# STM32_MCU.net
KiCad netlist of a schematic drawn in Altium Designer
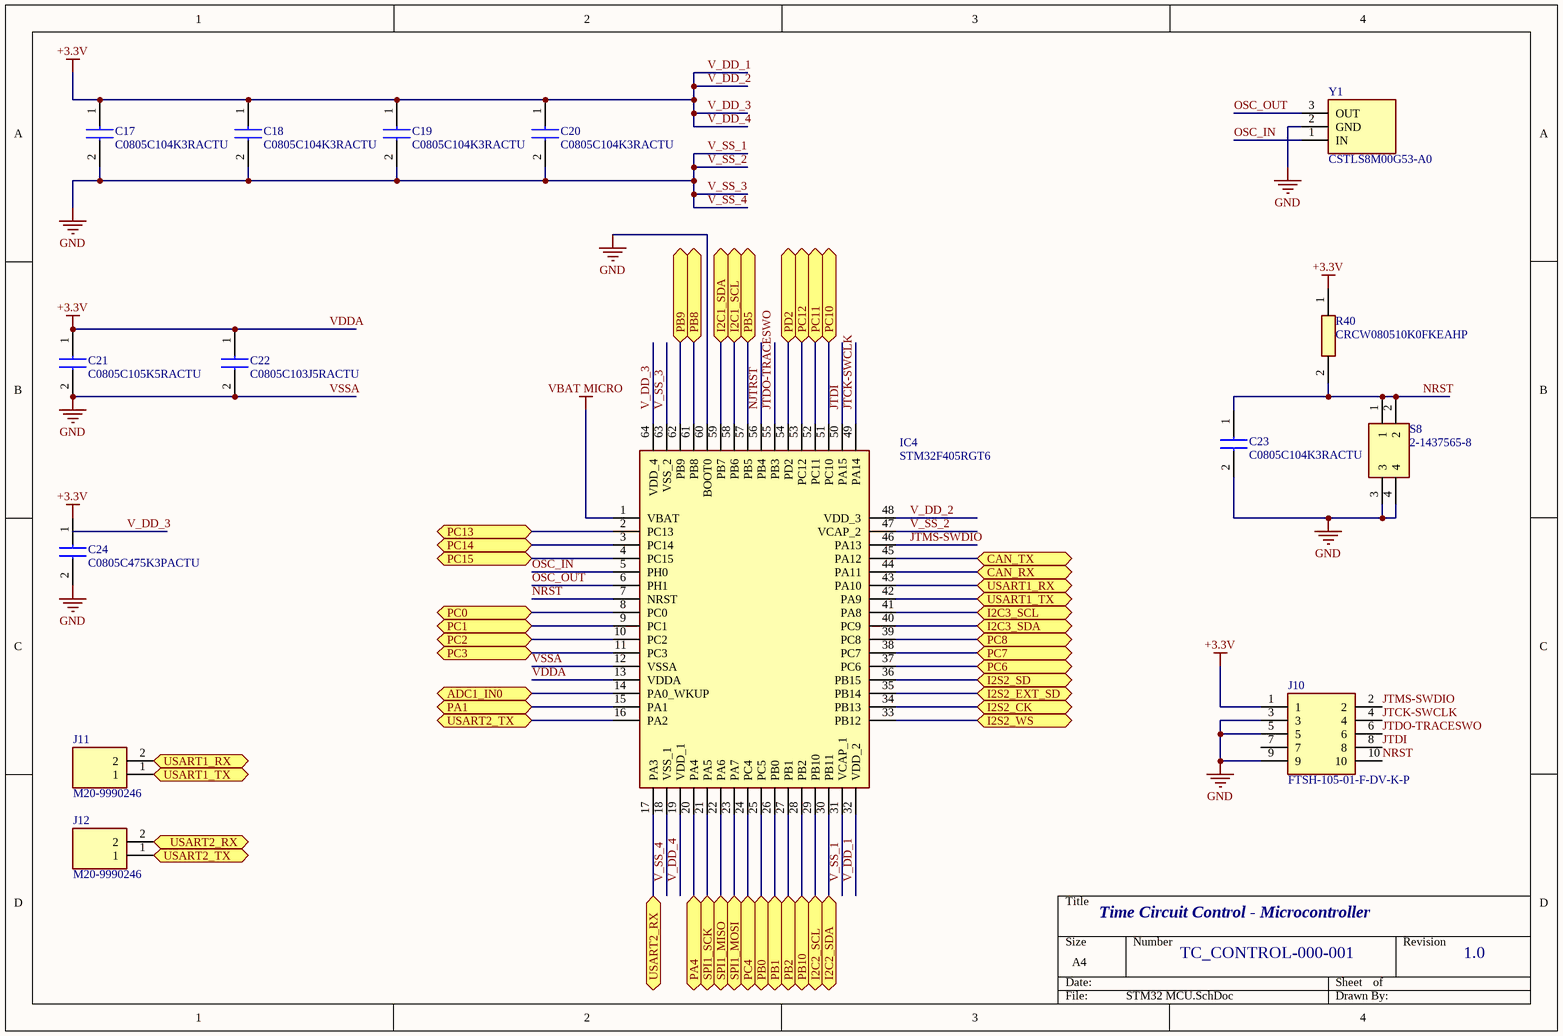
[diagram p0: STM32 MCU.SchDoc]

(export (version "E")
  (design (tool "Eeschema 10.0.6"))
  (components
    (comp (ref "C17")
      (value "C0805C104K3RACTU")
      (footprint "SamacSys:CAPC2012X88N")
      (description "Capacitor")
      (fields (field (name "MOUSER PART NUMBER") "80-C0805C104K3R"))
      (libsource (lib "SamacSys") (part "C0805C104K3RACTU"))
    )
    (comp (ref "C18")
      (value "C0805C104K3RACTU")
      (footprint "SamacSys:CAPC2012X88N")
      (description "Capacitor")
      (fields (field (name "MOUSER PART NUMBER") "80-C0805C104K3R"))
      (libsource (lib "SamacSys") (part "C0805C104K3RACTU"))
    )
    (comp (ref "C19")
      (value "C0805C104K3RACTU")
      (footprint "SamacSys:CAPC2012X88N")
      (description "Capacitor")
      (fields (field (name "MOUSER PART NUMBER") "80-C0805C104K3R"))
      (libsource (lib "SamacSys") (part "C0805C104K3RACTU"))
    )
    (comp (ref "C20")
      (value "C0805C104K3RACTU")
      (footprint "SamacSys:CAPC2012X88N")
      (description "Capacitor")
      (fields (field (name "MOUSER PART NUMBER") "80-C0805C104K3R"))
      (libsource (lib "SamacSys") (part "C0805C104K3RACTU"))
    )
    (comp (ref "C21")
      (value "C0805C105K5RACTU")
      (footprint "SamacSys:CAPC2012X140N")
      (description "Capacitor")
      (fields (field (name "MOUSER PART NUMBER") "80-C0805C105K5R"))
      (libsource (lib "SamacSys") (part "C0805C105K5RACTU"))
    )
    (comp (ref "C22")
      (value "C0805C103J5RACTU")
      (footprint "SamacSys:CAPC2012X88N")
      (description "Capacitor")
      (fields (field (name "MOUSER PART NUMBER") "80-C0805C103J5R"))
      (libsource (lib "SamacSys") (part "C0805C103J5RACTU"))
    )
    (comp (ref "C23")
      (value "C0805C104K3RACTU")
      (footprint "SamacSys:CAPC2012X88N")
      (description "Capacitor")
      (fields (field (name "MOUSER PART NUMBER") "80-C0805C104K3R"))
      (libsource (lib "SamacSys") (part "C0805C104K3RACTU"))
    )
    (comp (ref "C24")
      (value "C0805C475K3PACTU")
      (footprint "SamacSys:CAPC2013X140N")
      (description "Capacitor")
      (fields (field (name "MOUSER PART NUMBER") "80-C0805C475K3P"))
      (libsource (lib "SamacSys") (part "C0805C475K3PACTU"))
    )
    (comp (ref "IC4")
      (value "STM32F405RGT6")
      (footprint "SamacSys:QFP50P1200X1200X160-64N")
      (description "Integrated Circuit")
      (fields (field (name "MOUSER PART NUMBER") "511-STM32F405RGT6"))
      (libsource (lib "SamacSys") (part "STM32F405RGT6"))
    )
    (comp (ref "J10")
      (value "FTSH-105-01-F-DV-K-P")
      (footprint "SamacSys:FTSH-105-XX-YYY-DV-K-P")
      (description "Connector")
      (fields (field (name "MOUSER PART NUMBER") "200-FTSH10501FDVKP"))
      (libsource (lib "SamacSys") (part "FTSH-105-01-F-DV-K-P"))
    )
    (comp (ref "J11")
      (value "M20-9990246")
      (footprint "SamacSys:HDRV2W66P0X254_1X2_508X254X874P")
      (description "Connector")
      (fields (field (name "MOUSER PART NUMBER") "855-M20-9990246"))
      (libsource (lib "SamacSys") (part "M20-9990246"))
    )
    (comp (ref "J12")
      (value "M20-9990246")
      (footprint "SamacSys:HDRV2W66P0X254_1X2_508X254X874P")
      (description "Connector")
      (fields (field (name "MOUSER PART NUMBER") "855-M20-9990246"))
      (libsource (lib "SamacSys") (part "M20-9990246"))
    )
    (comp (ref "R40")
      (value "CRCW080510K0FKEAHP")
      (footprint "SamacSys:RESC2012X60N")
      (description "Resistor")
      (fields (field (name "MOUSER PART NUMBER") "71-CRCW080510K0FKEAH"))
      (libsource (lib "SamacSys") (part "CRCW080510K0FKEAHP"))
    )
    (comp (ref "S8")
      (value "2-1437565-8")
      (footprint "SamacSys:FSM2J_1")
      (description "Switch")
      (fields (field (name "MOUSER PART NUMBER") "506-2-1437565-8"))
      (libsource (lib "SamacSys") (part "2-1437565-8"))
    )
    (comp (ref "Y1")
      (value "CSTLS8M00G53-A0")
      (footprint "SamacSys:CSTLS8M00G53A0")
      (description "Crystal or Oscillator")
      (fields (field (name "MOUSER PART NUMBER") "81-CSTLS8M00G53-A0"))
      (libsource (lib "SamacSys") (part "CSTLS8M00G53-A0"))
    )
  )
  (nets
    (net (code "1") (name "+3.3V") (class "Default")
      (node (ref "C17") (pin "1") (pinfunction "1_1") (pintype "passive"))
      (node (ref "C18") (pin "1") (pinfunction "1_1") (pintype "passive"))
      (node (ref "C19") (pin "1") (pinfunction "1_1") (pintype "passive"))
      (node (ref "C20") (pin "1") (pinfunction "1_1") (pintype "passive"))
      (node (ref "C21") (pin "1") (pinfunction "1_1") (pintype "passive"))
      (node (ref "C22") (pin "1") (pinfunction "1_1") (pintype "passive"))
      (node (ref "C24") (pin "1") (pinfunction "C1_1") (pintype "passive"))
      (node (ref "IC4") (pin "13") (pinfunction "VDDA_13") (pintype "passive"))
      (node (ref "IC4") (pin "19") (pinfunction "VDD_1_19") (pintype "passive"))
      (node (ref "IC4") (pin "32") (pinfunction "VDD_2_32") (pintype "passive"))
      (node (ref "IC4") (pin "48") (pinfunction "VDD_3_48") (pintype "passive"))
      (node (ref "IC4") (pin "64") (pinfunction "VDD_4_64") (pintype "passive"))
      (node (ref "J10") (pin "1") (pinfunction "1_1") (pintype "passive"))
      (node (ref "R40") (pin "1") (pinfunction "1_1") (pintype "passive"))
    )
    (net (code "2") (name "/ADC1_IN0") (class "Default")
      (node (ref "IC4") (pin "14") (pinfunction "PA0_WKUP_14") (pintype "passive"))
    )
    (net (code "3") (name "/CAN_RX") (class "Default")
      (node (ref "IC4") (pin "44") (pinfunction "PA11_44") (pintype "passive"))
    )
    (net (code "4") (name "/CAN_TX") (class "Default")
      (node (ref "IC4") (pin "45") (pinfunction "PA12_45") (pintype "passive"))
    )
    (net (code "5") (name "/I2C1_SCL") (class "Default")
      (node (ref "IC4") (pin "58") (pinfunction "PB6_58") (pintype "passive"))
    )
    (net (code "6") (name "/I2C1_SDA") (class "Default")
      (node (ref "IC4") (pin "59") (pinfunction "PB7_59") (pintype "passive"))
    )
    (net (code "7") (name "/I2C2_SCL") (class "Default")
      (node (ref "IC4") (pin "29") (pinfunction "PB10_29") (pintype "passive"))
    )
    (net (code "8") (name "/I2C2_SDA") (class "Default")
      (node (ref "IC4") (pin "30") (pinfunction "PB11_30") (pintype "passive"))
    )
    (net (code "9") (name "/I2C3_SCL") (class "Default")
      (node (ref "IC4") (pin "41") (pinfunction "PA8_41") (pintype "passive"))
    )
    (net (code "10") (name "/I2C3_SDA") (class "Default")
      (node (ref "IC4") (pin "40") (pinfunction "PC9_40") (pintype "passive"))
    )
    (net (code "11") (name "/I2S2_CK") (class "Default")
      (node (ref "IC4") (pin "34") (pinfunction "PB13_34") (pintype "passive"))
    )
    (net (code "12") (name "/I2S2_EXT_SD") (class "Default")
      (node (ref "IC4") (pin "35") (pinfunction "PB14_35") (pintype "passive"))
    )
    (net (code "13") (name "/I2S2_SD") (class "Default")
      (node (ref "IC4") (pin "36") (pinfunction "PB15_36") (pintype "passive"))
    )
    (net (code "14") (name "/I2S2_WS") (class "Default")
      (node (ref "IC4") (pin "33") (pinfunction "PB12_33") (pintype "passive"))
    )
    (net (code "15") (name "/JTCK-SWCLK") (class "Default")
      (node (ref "IC4") (pin "49") (pinfunction "PA14_49") (pintype "passive"))
      (node (ref "J10") (pin "4") (pinfunction "4_4") (pintype "passive"))
    )
    (net (code "16") (name "/JTDI") (class "Default")
      (node (ref "IC4") (pin "50") (pinfunction "PA15_50") (pintype "passive"))
      (node (ref "J10") (pin "8") (pinfunction "8_8") (pintype "passive"))
    )
    (net (code "17") (name "/JTDO-TRACESWO") (class "Default")
      (node (ref "IC4") (pin "55") (pinfunction "PB3_55") (pintype "passive"))
      (node (ref "J10") (pin "6") (pinfunction "6_6") (pintype "passive"))
    )
    (net (code "18") (name "/JTMS-SWDIO") (class "Default")
      (node (ref "IC4") (pin "46") (pinfunction "PA13_46") (pintype "passive"))
      (node (ref "J10") (pin "2") (pinfunction "2_2") (pintype "passive"))
    )
    (net (code "19") (name "/NJTRST") (class "Default")
      (node (ref "IC4") (pin "56") (pinfunction "PB4_56") (pintype "passive"))
    )
    (net (code "20") (name "/NRST") (class "Default")
      (node (ref "C23") (pin "1") (pinfunction "1_1") (pintype "passive"))
      (node (ref "IC4") (pin "7") (pinfunction "NRST_7") (pintype "passive"))
      (node (ref "J10") (pin "10") (pinfunction "10_10") (pintype "passive"))
      (node (ref "R40") (pin "2") (pinfunction "2_2") (pintype "passive"))
      (node (ref "S8") (pin "1") (pinfunction "1_1") (pintype "passive"))
      (node (ref "S8") (pin "2") (pinfunction "2_2") (pintype "passive"))
    )
    (net (code "21") (name "/OSC_IN") (class "Default")
      (node (ref "IC4") (pin "5") (pinfunction "PH0_5") (pintype "passive"))
      (node (ref "Y1") (pin "1") (pinfunction "IN_1") (pintype "passive"))
    )
    (net (code "22") (name "/OSC_OUT") (class "Default")
      (node (ref "IC4") (pin "6") (pinfunction "PH1_6") (pintype "passive"))
      (node (ref "Y1") (pin "3") (pinfunction "OUT_3") (pintype "passive"))
    )
    (net (code "23") (name "/PA1") (class "Default")
      (node (ref "IC4") (pin "15") (pinfunction "PA1_15") (pintype "passive"))
    )
    (net (code "24") (name "/PA4") (class "Default")
      (node (ref "IC4") (pin "20") (pinfunction "PA4_20") (pintype "passive"))
    )
    (net (code "25") (name "/PB0") (class "Default")
      (node (ref "IC4") (pin "25") (pinfunction "PC5_25") (pintype "passive"))
    )
    (net (code "26") (name "/PB1") (class "Default")
      (node (ref "IC4") (pin "26") (pinfunction "PB0_26") (pintype "passive"))
    )
    (net (code "27") (name "/PB2") (class "Default")
      (node (ref "IC4") (pin "27") (pinfunction "PB1_27") (pintype "passive"))
    )
    (net (code "28") (name "/PB5") (class "Default")
      (node (ref "IC4") (pin "57") (pinfunction "PB5_57") (pintype "passive"))
    )
    (net (code "29") (name "/PB8") (class "Default")
      (node (ref "IC4") (pin "61") (pinfunction "PB8_61") (pintype "passive"))
    )
    (net (code "30") (name "/PB9") (class "Default")
      (node (ref "IC4") (pin "62") (pinfunction "PB9_62") (pintype "passive"))
    )
    (net (code "31") (name "/PB10") (class "Default")
      (node (ref "IC4") (pin "28") (pinfunction "PB2_28") (pintype "passive"))
    )
    (net (code "32") (name "/PC0") (class "Default")
      (node (ref "IC4") (pin "8") (pinfunction "PC0_8") (pintype "passive"))
    )
    (net (code "33") (name "/PC1") (class "Default")
      (node (ref "IC4") (pin "9") (pinfunction "PC1_9") (pintype "passive"))
    )
    (net (code "34") (name "/PC2") (class "Default")
      (node (ref "IC4") (pin "10") (pinfunction "PC2_10") (pintype "passive"))
    )
    (net (code "35") (name "/PC3") (class "Default")
      (node (ref "IC4") (pin "11") (pinfunction "PC3_11") (pintype "passive"))
    )
    (net (code "36") (name "/PC4") (class "Default")
      (node (ref "IC4") (pin "24") (pinfunction "PC4_24") (pintype "passive"))
    )
    (net (code "37") (name "/PC6") (class "Default")
      (node (ref "IC4") (pin "37") (pinfunction "PC6_37") (pintype "passive"))
    )
    (net (code "38") (name "/PC7") (class "Default")
      (node (ref "IC4") (pin "38") (pinfunction "PC7_38") (pintype "passive"))
    )
    (net (code "39") (name "/PC8") (class "Default")
      (node (ref "IC4") (pin "39") (pinfunction "PC8_39") (pintype "passive"))
    )
    (net (code "40") (name "/PC10") (class "Default")
      (node (ref "IC4") (pin "51") (pinfunction "PC10_51") (pintype "passive"))
    )
    (net (code "41") (name "/PC11") (class "Default")
      (node (ref "IC4") (pin "52") (pinfunction "PC11_52") (pintype "passive"))
    )
    (net (code "42") (name "/PC12") (class "Default")
      (node (ref "IC4") (pin "53") (pinfunction "PC12_53") (pintype "passive"))
    )
    (net (code "43") (name "/PC13") (class "Default")
      (node (ref "IC4") (pin "2") (pinfunction "PC13_2") (pintype "passive"))
    )
    (net (code "44") (name "/PC14") (class "Default")
      (node (ref "IC4") (pin "3") (pinfunction "PC14_3") (pintype "passive"))
    )
    (net (code "45") (name "/PC15") (class "Default")
      (node (ref "IC4") (pin "4") (pinfunction "PC15_4") (pintype "passive"))
    )
    (net (code "46") (name "/PD2") (class "Default")
      (node (ref "IC4") (pin "54") (pinfunction "PD2_54") (pintype "passive"))
    )
    (net (code "47") (name "/SPI1_MISO") (class "Default")
      (node (ref "IC4") (pin "22") (pinfunction "PA6_22") (pintype "passive"))
    )
    (net (code "48") (name "/SPI1_MOSI") (class "Default")
      (node (ref "IC4") (pin "23") (pinfunction "PA7_23") (pintype "passive"))
    )
    (net (code "49") (name "/SPI1_SCK") (class "Default")
      (node (ref "IC4") (pin "21") (pinfunction "PA5_21") (pintype "passive"))
    )
    (net (code "50") (name "/USART1_RX") (class "Default")
      (node (ref "IC4") (pin "43") (pinfunction "PA10_43") (pintype "passive"))
      (node (ref "J11") (pin "2") (pinfunction "2_2") (pintype "passive"))
    )
    (net (code "51") (name "/USART1_TX") (class "Default")
      (node (ref "IC4") (pin "42") (pinfunction "PA9_42") (pintype "passive"))
      (node (ref "J11") (pin "1") (pinfunction "1_1") (pintype "passive"))
    )
    (net (code "52") (name "/USART2_RX") (class "Default")
      (node (ref "IC4") (pin "17") (pinfunction "PA3_17") (pintype "passive"))
      (node (ref "J12") (pin "2") (pinfunction "2_2") (pintype "passive"))
    )
    (net (code "53") (name "/USART2_TX") (class "Default")
      (node (ref "IC4") (pin "16") (pinfunction "PA2_16") (pintype "passive"))
      (node (ref "J12") (pin "1") (pinfunction "1_1") (pintype "passive"))
    )
    (net (code "54") (name "GND") (class "Default")
      (node (ref "C17") (pin "2") (pinfunction "2_2") (pintype "passive"))
      (node (ref "C18") (pin "2") (pinfunction "2_2") (pintype "passive"))
      (node (ref "C19") (pin "2") (pinfunction "2_2") (pintype "passive"))
      (node (ref "C20") (pin "2") (pinfunction "2_2") (pintype "passive"))
      (node (ref "C21") (pin "2") (pinfunction "2_2") (pintype "passive"))
      (node (ref "C22") (pin "2") (pinfunction "2_2") (pintype "passive"))
      (node (ref "C23") (pin "2") (pinfunction "2_2") (pintype "passive"))
      (node (ref "C24") (pin "2") (pinfunction "C2_2") (pintype "passive"))
      (node (ref "IC4") (pin "12") (pinfunction "VSSA_12") (pintype "passive"))
      (node (ref "IC4") (pin "18") (pinfunction "VSS_1_18") (pintype "passive"))
      (node (ref "IC4") (pin "31") (pinfunction "VCAP_1_31") (pintype "passive"))
      (node (ref "IC4") (pin "47") (pinfunction "VCAP_2_47") (pintype "passive"))
      (node (ref "IC4") (pin "60") (pinfunction "BOOT0_60") (pintype "passive"))
      (node (ref "IC4") (pin "63") (pinfunction "VSS_2_63") (pintype "passive"))
      (node (ref "J10") (pin "3") (pinfunction "3_3") (pintype "passive"))
      (node (ref "J10") (pin "5") (pinfunction "5_5") (pintype "passive"))
      (node (ref "J10") (pin "9") (pinfunction "9_9") (pintype "passive"))
      (node (ref "S8") (pin "3") (pinfunction "3_3") (pintype "passive"))
      (node (ref "S8") (pin "4") (pinfunction "4_4") (pintype "passive"))
      (node (ref "Y1") (pin "2") (pinfunction "GND_2") (pintype "passive"))
    )
    (net (code "55") (name "VBAT MICRO") (class "Default")
      (node (ref "IC4") (pin "1") (pinfunction "VBAT_1") (pintype "passive"))
    )
    (net (code "56") (name "unconnected-(J10-Pad7)") (class "Default")
      (node (ref "J10") (pin "7") (pinfunction "7_7") (pintype "passive"))
    )
  )
)
